# SD_Card_WCN_RF.net
KiCad netlist of a schematic drawn in Altium Designer
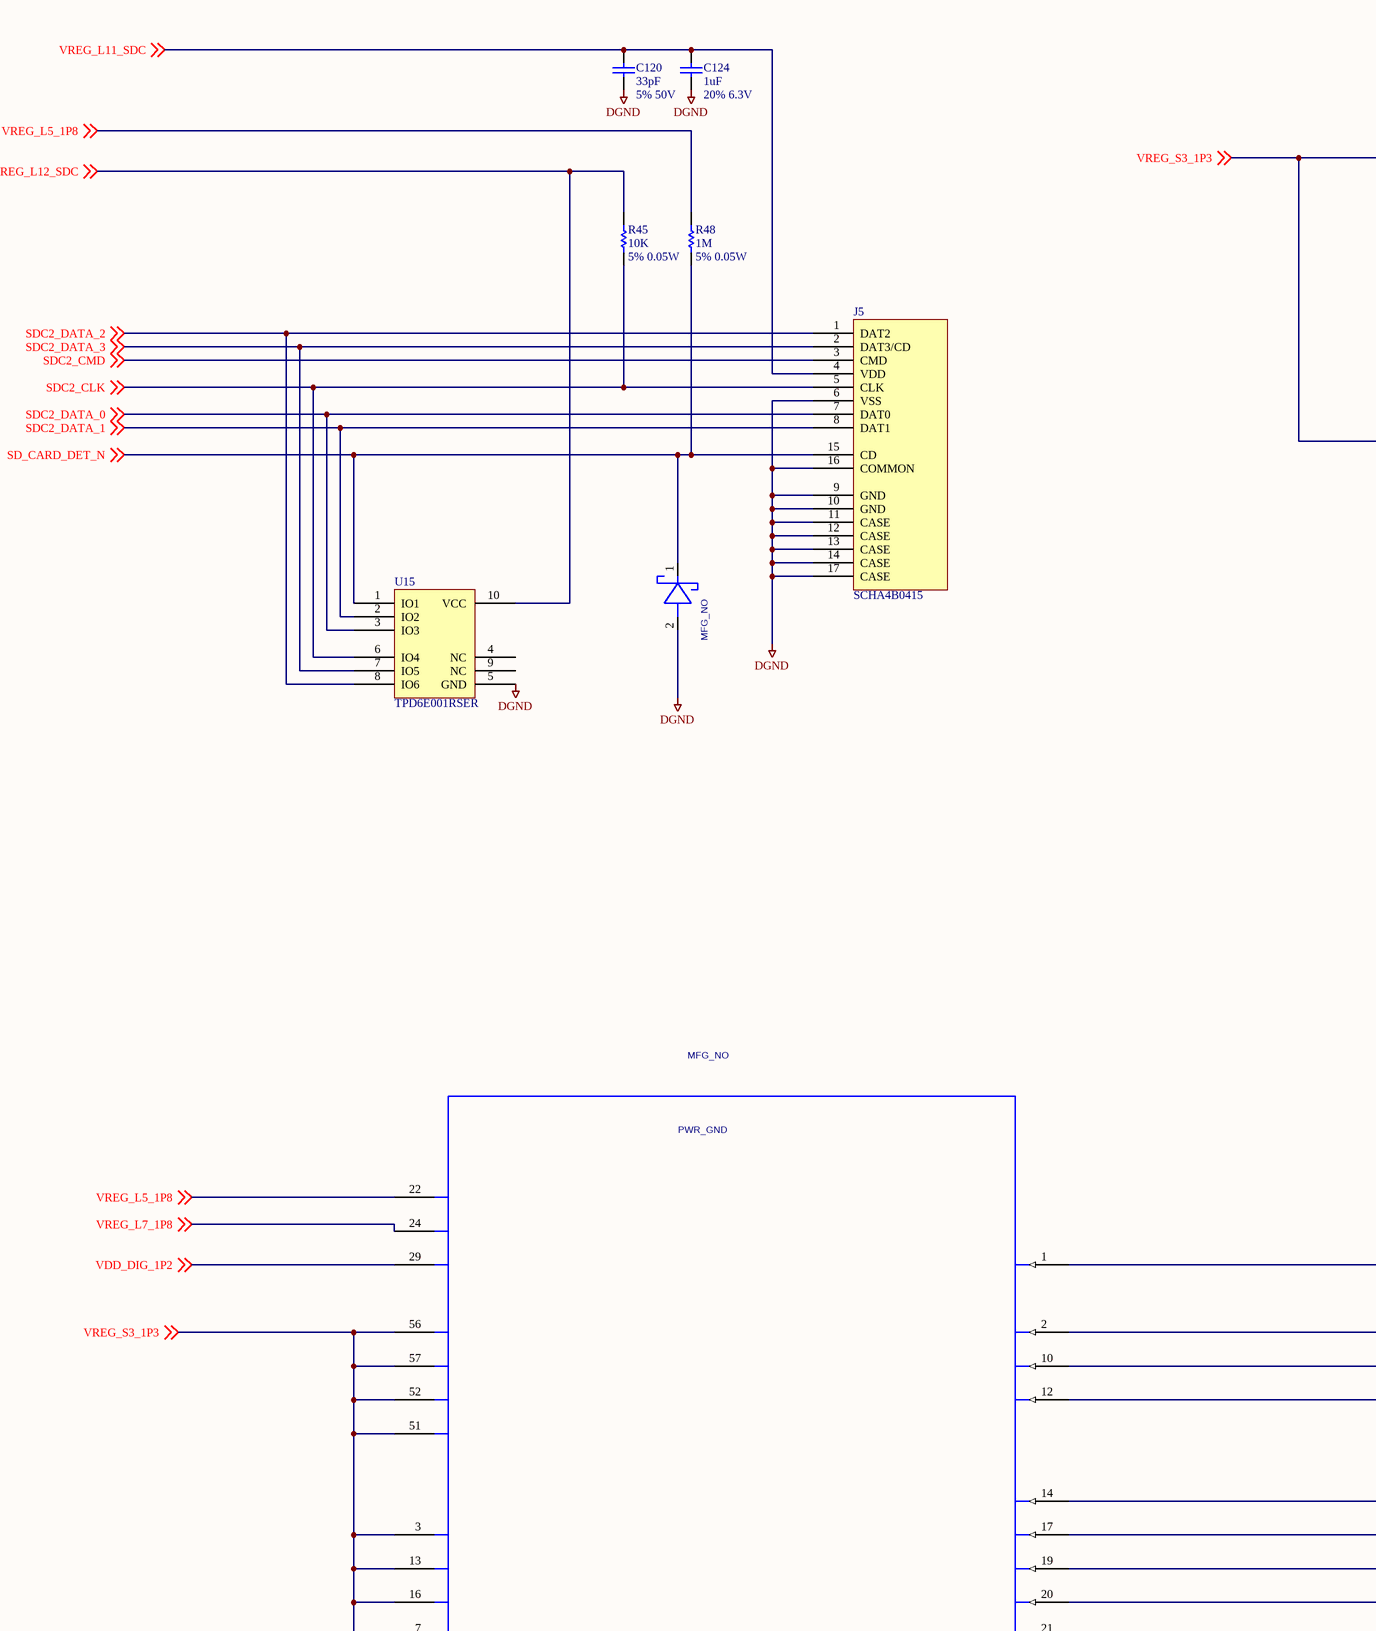
[diagram p0: SD Card_WCN_RF.SchDoc, top left]
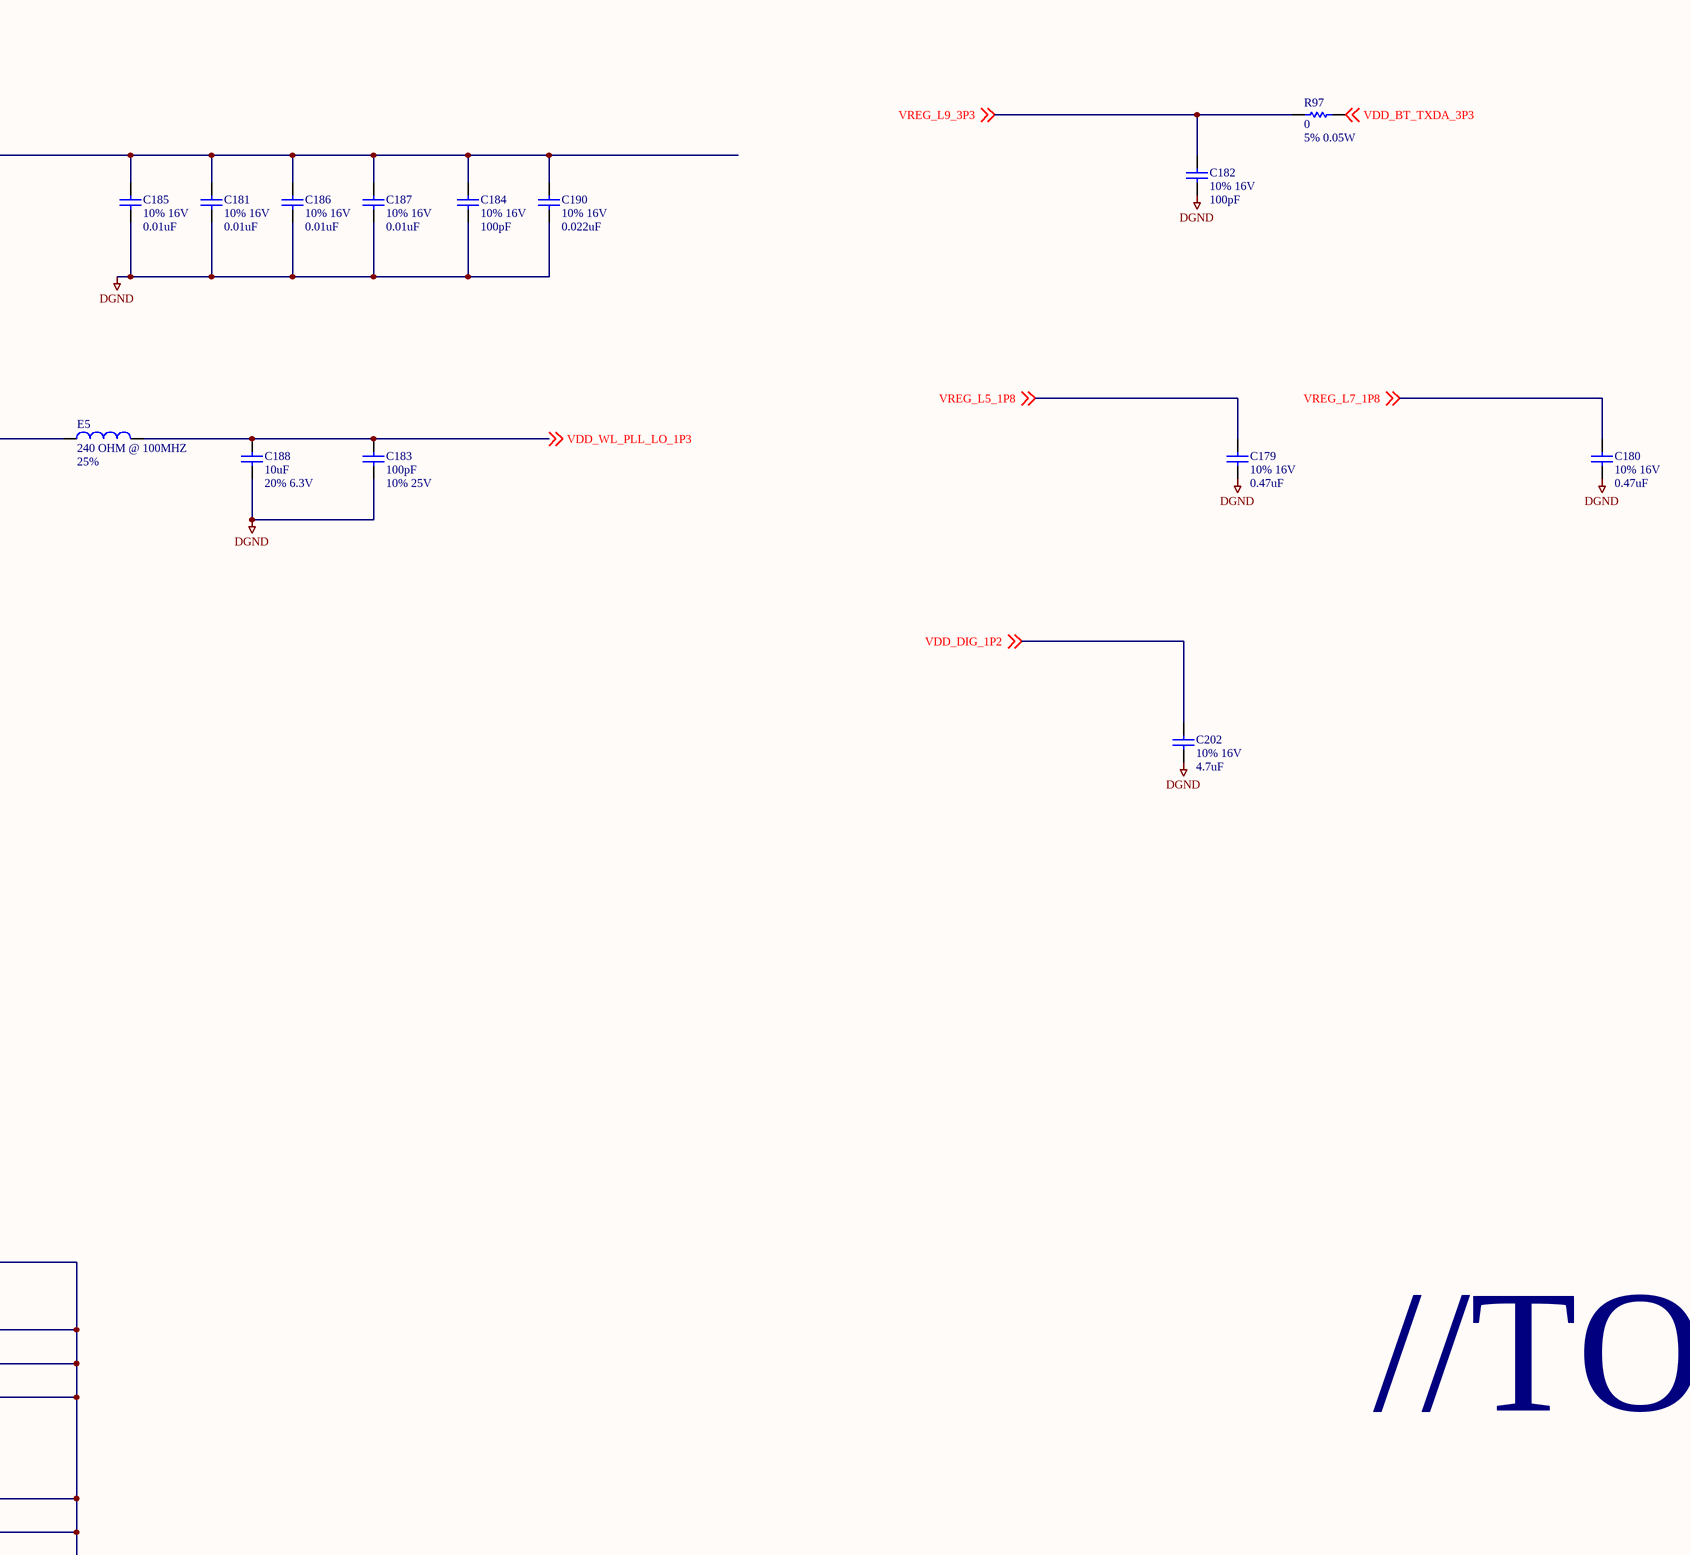
[diagram p1: SD Card_WCN_RF.SchDoc, top middle]
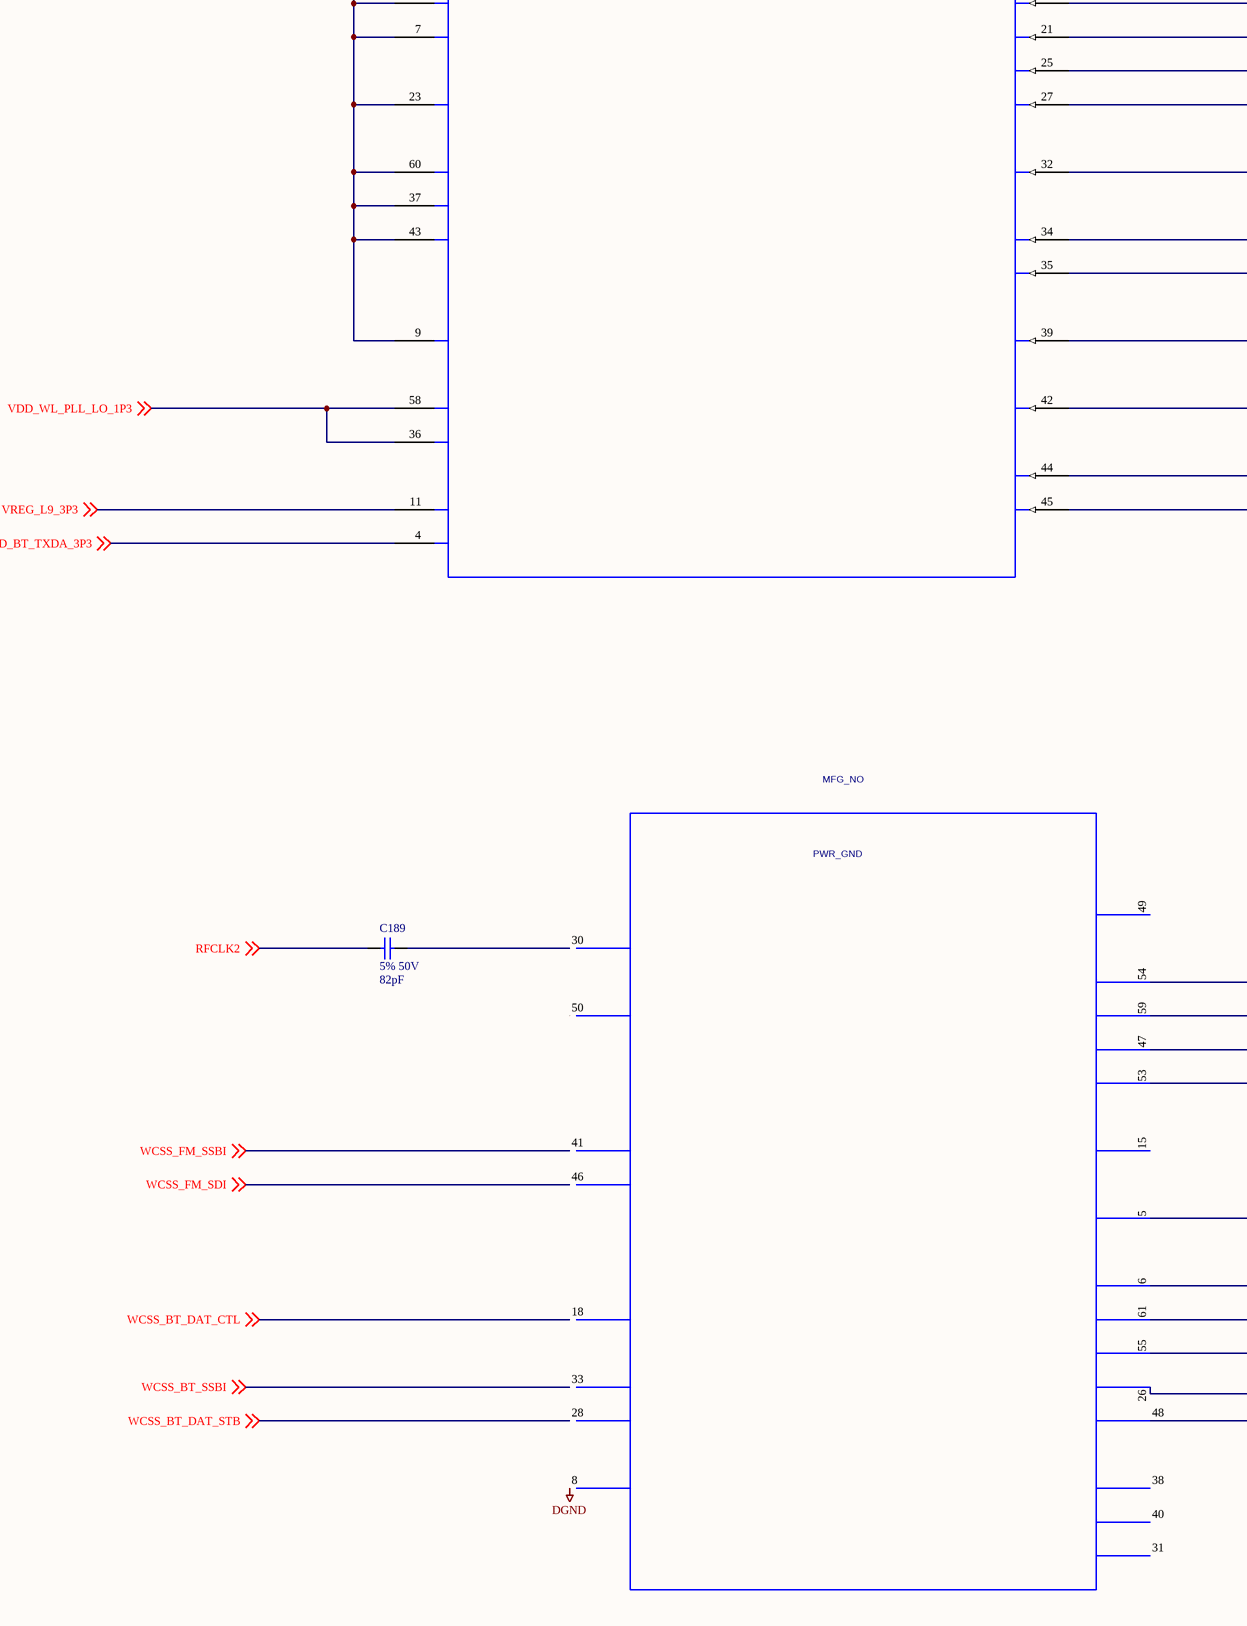
[diagram p2: SD Card_WCN_RF.SchDoc, bottom left]
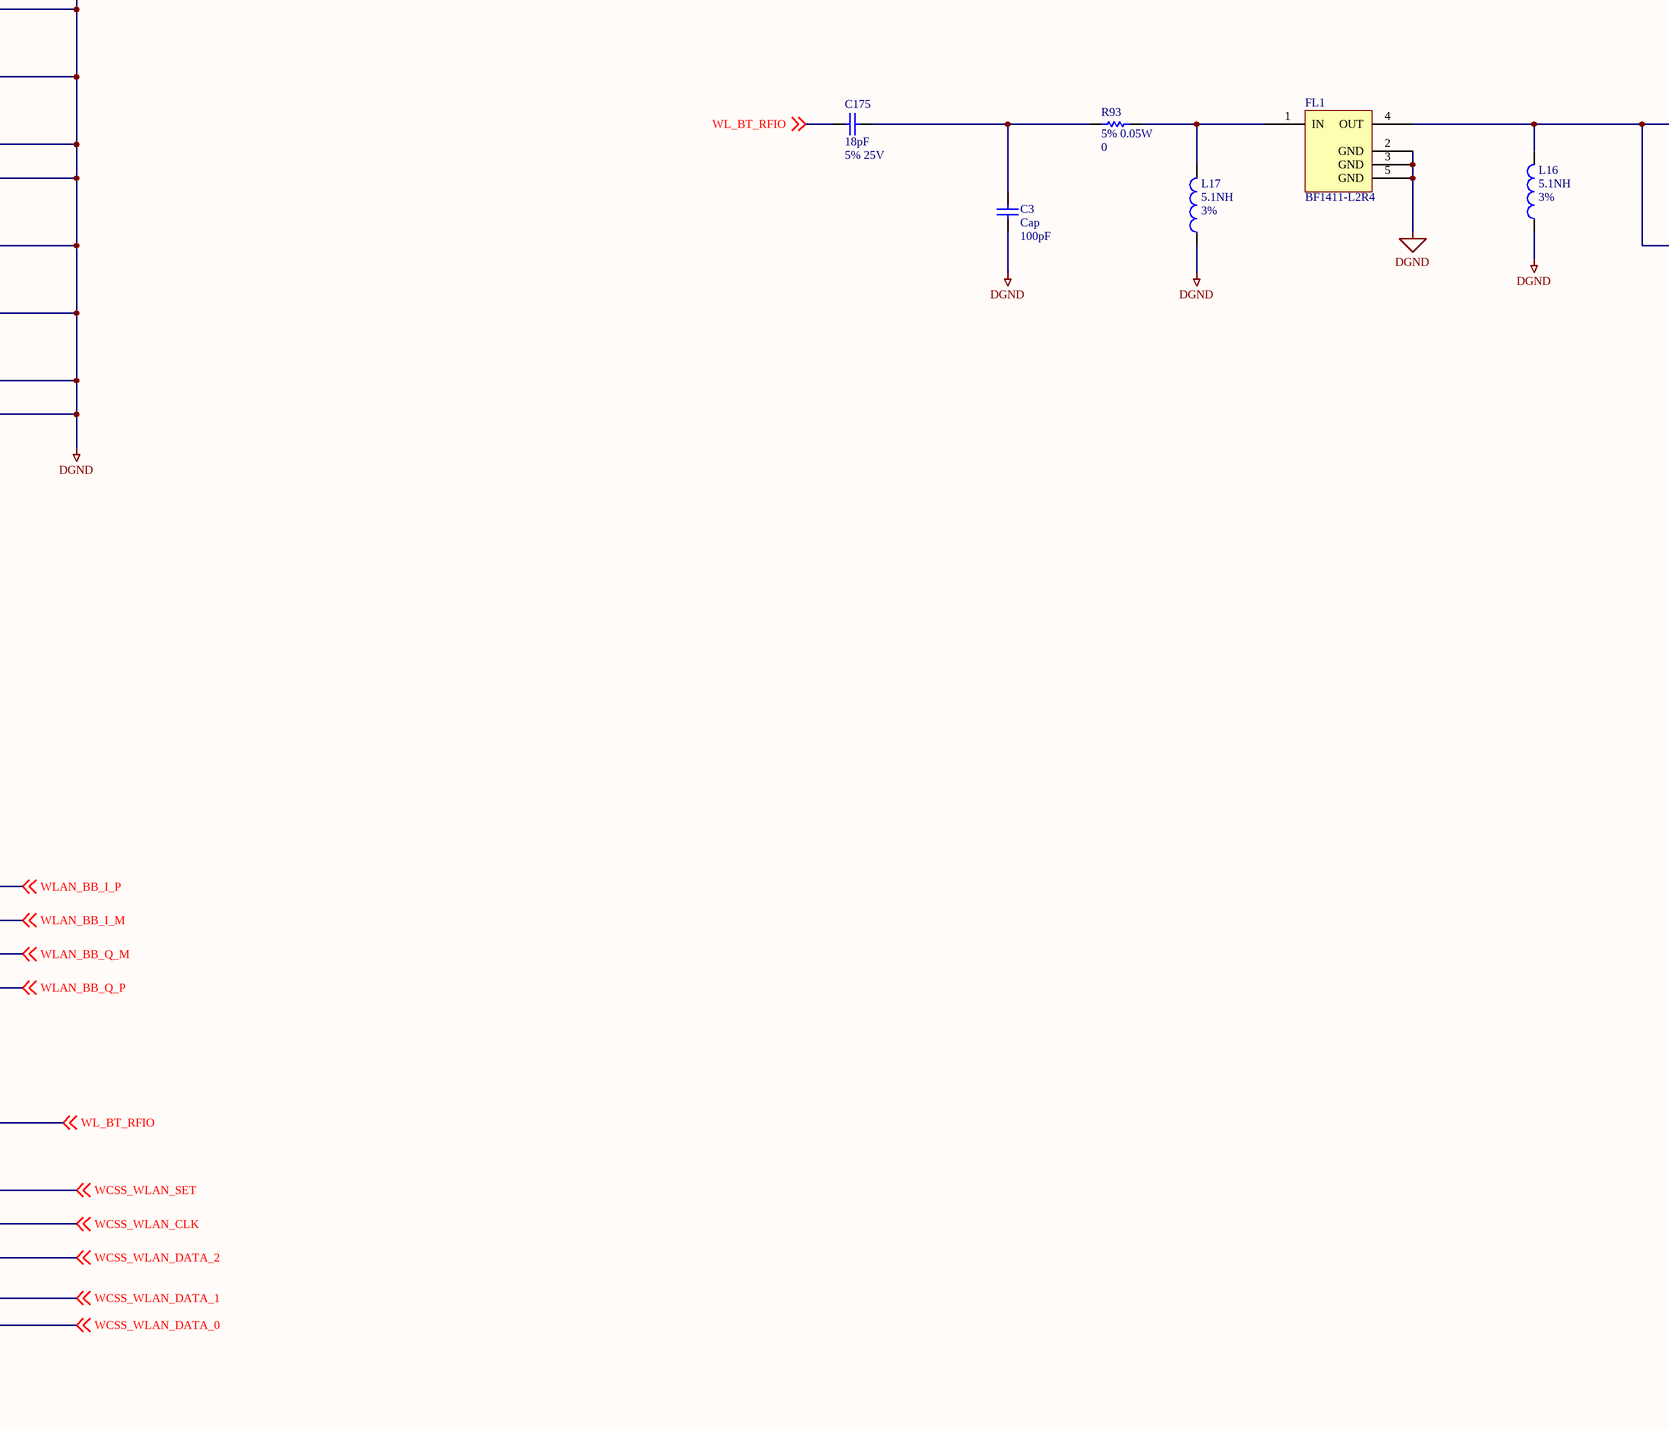
[diagram p3: SD Card_WCN_RF.SchDoc, bottom middle]
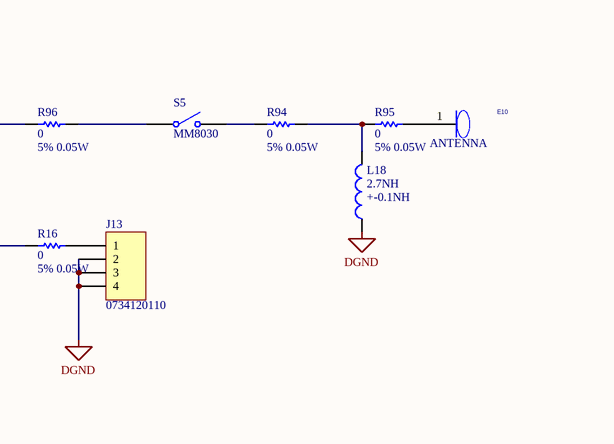
[diagram p4: SD Card_WCN_RF.SchDoc, bottom right]

(export (version "E")
  (design (tool "Eeschema 10.0.6"))
  (components
    (comp (ref "C3")
      (value "Cap")
      (footprint "RAD-0.3")
      (description "Capacitor")
      (fields (field (name "ALTIUM_VALUE") "100pF") (field (name "PUBLISHER") "Altium Limited"))
      (libsource (lib "Miscellaneous Devices") (part "Cap"))
    )
    (comp (ref "C120")
      (value "33pF")
      (footprint "C0402")
      (description "Capacitor")
      (fields (field (name "ALTIUM_VALUE") "5% 50V") (field (name "PUBLISHER") "Altium Limited"))
      (libsource (lib "Miscellaneous Devices") (part "Cap"))
    )
    (comp (ref "C124")
      (value "1uF")
      (footprint "C0402")
      (description "Capacitor")
      (fields (field (name "ALTIUM_VALUE") "20% 6.3V") (field (name "PUBLISHER") "Altium Limited"))
      (libsource (lib "Miscellaneous Devices") (part "Cap"))
    )
    (comp (ref "C175")
      (value "18pF")
      (footprint "RAD-0.3")
      (description "Capacitor")
      (fields (field (name "ALTIUM_VALUE") "5% 25V") (field (name "PUBLISHER") "Altium Limited"))
      (libsource (lib "Miscellaneous Devices") (part "Cap"))
    )
    (comp (ref "C179")
      (value "10% 16V")
      (footprint "C0402")
      (description "Capacitor")
      (fields (field (name "ALTIUM_VALUE") "0.47uF") (field (name "PUBLISHER") "Altium Limited"))
      (libsource (lib "Miscellaneous Devices") (part "Cap"))
    )
    (comp (ref "C180")
      (value "10% 16V")
      (footprint "C0402")
      (description "Capacitor")
      (fields (field (name "ALTIUM_VALUE") "0.47uF") (field (name "PUBLISHER") "Altium Limited"))
      (libsource (lib "Miscellaneous Devices") (part "Cap"))
    )
    (comp (ref "C181")
      (value "10% 16V")
      (footprint "C0402")
      (description "Capacitor")
      (fields (field (name "ALTIUM_VALUE") "0.01uF") (field (name "PUBLISHER") "Altium Limited"))
      (libsource (lib "Miscellaneous Devices") (part "Cap"))
    )
    (comp (ref "C182")
      (value "10% 16V")
      (footprint "C0402")
      (description "Capacitor")
      (fields (field (name "ALTIUM_VALUE") "100pF") (field (name "PUBLISHER") "Altium Limited"))
      (libsource (lib "Miscellaneous Devices") (part "Cap"))
    )
    (comp (ref "C183")
      (value "100pF")
      (footprint "C0402")
      (description "Capacitor")
      (fields (field (name "ALTIUM_VALUE") "10% 25V") (field (name "PUBLISHER") "Altium Limited"))
      (libsource (lib "Miscellaneous Devices") (part "Cap"))
    )
    (comp (ref "C184")
      (value "10% 16V")
      (footprint "C0402")
      (description "Capacitor")
      (fields (field (name "ALTIUM_VALUE") "100pF") (field (name "PUBLISHER") "Altium Limited"))
      (libsource (lib "Miscellaneous Devices") (part "Cap"))
    )
    (comp (ref "C185")
      (value "10% 16V")
      (footprint "C0402")
      (description "Capacitor")
      (fields (field (name "ALTIUM_VALUE") "0.01uF") (field (name "PUBLISHER") "Altium Limited"))
      (libsource (lib "Miscellaneous Devices") (part "Cap"))
    )
    (comp (ref "C186")
      (value "10% 16V")
      (footprint "C0402")
      (description "Capacitor")
      (fields (field (name "ALTIUM_VALUE") "0.01uF") (field (name "PUBLISHER") "Altium Limited"))
      (libsource (lib "Miscellaneous Devices") (part "Cap"))
    )
    (comp (ref "C187")
      (value "10% 16V")
      (footprint "C0402")
      (description "Capacitor")
      (fields (field (name "ALTIUM_VALUE") "0.01uF") (field (name "PUBLISHER") "Altium Limited"))
      (libsource (lib "Miscellaneous Devices") (part "Cap"))
    )
    (comp (ref "C188")
      (value "10uF")
      (footprint "C0402")
      (description "Capacitor")
      (fields (field (name "ALTIUM_VALUE") "20% 6.3V") (field (name "PUBLISHER") "Altium Limited"))
      (libsource (lib "Miscellaneous Devices") (part "Cap"))
    )
    (comp (ref "C189")
      (value "5% 50V")
      (footprint "C0402")
      (description "Capacitor")
      (fields (field (name "ALTIUM_VALUE") "82pF") (field (name "PUBLISHER") "Altium Limited"))
      (libsource (lib "Miscellaneous Devices") (part "Cap"))
    )
    (comp (ref "C190")
      (value "10% 16V")
      (footprint "C0402")
      (description "Capacitor")
      (fields (field (name "ALTIUM_VALUE") "0.022uF") (field (name "PUBLISHER") "Altium Limited"))
      (libsource (lib "Miscellaneous Devices") (part "Cap"))
    )
    (comp (ref "C202")
      (value "10% 16V")
      (footprint "C0402")
      (description "Capacitor")
      (fields (field (name "ALTIUM_VALUE") "4.7uF") (field (name "PUBLISHER") "Altium Limited"))
      (libsource (lib "Miscellaneous Devices") (part "Cap"))
    )
    (comp (ref "CR24")
      (value "ESD7C5")
      (footprint "c0402")
      (fields (field (name "PART_NUMBER") "MCN_NO") (field (name "PART_ID") "MFG_NO"))
      (libsource (lib "MSM8916_DRAM_PMIC_REF_Library") (part "SCHOTTKY"))
    )
    (comp (ref "E5")
      (value "240 OHM @ 100MHZ")
      (footprint "0402-A")
      (description "Inductor")
      (fields (field (name "ALTIUM_VALUE") "25%") (field (name "PUBLISHER") "Altium Limited"))
      (libsource (lib "Miscellaneous Devices") (part "Inductor"))
    )
    (comp (ref "E10")
      (value "ANTENNA")
      (footprint "TP")
      (libsource (lib "MSM8916_DRAM_PMIC_REF_Library") (part "TP"))
    )
    (comp (ref "FL1")
      (value "BF1411-L2R4")
      (libsource (lib "MSM8916_DRAM_PMIC_REF_Library") (part "BF1411-L2R4"))
    )
    (comp (ref "J5")
      (value "SCHA4B0415")
      (footprint "c0402")
      (libsource (lib "MSM8916_DRAM_PMIC_REF_Library") (part "SCHA4B0415"))
    )
    (comp (ref "J13")
      (value "0734120110")
      (footprint "HDR1X4")
      (description "Header, 4-Pin")
      (fields (field (name "PUBLISHER") "Altium Limited"))
      (libsource (lib "Miscellaneous Connectors") (part "Header 4"))
    )
    (comp (ref "L16")
      (value "5.1NH")
      (footprint "0402-A")
      (description "Inductor")
      (fields (field (name "ALTIUM_VALUE") "3%") (field (name "PUBLISHER") "Altium Limited"))
      (libsource (lib "Miscellaneous Devices") (part "Inductor"))
    )
    (comp (ref "L17")
      (value "5.1NH")
      (footprint "0402-A")
      (description "Inductor")
      (fields (field (name "ALTIUM_VALUE") "3%") (field (name "PUBLISHER") "Altium Limited"))
      (libsource (lib "Miscellaneous Devices") (part "Inductor"))
    )
    (comp (ref "L18")
      (value "2.7NH")
      (footprint "0402-A")
      (description "Inductor")
      (fields (field (name "ALTIUM_VALUE") "+-0.1NH") (field (name "PUBLISHER") "Altium Limited"))
      (libsource (lib "Miscellaneous Devices") (part "Inductor"))
    )
    (comp (ref "R16")
      (value "0")
      (footprint "AXIAL-0.3")
      (description "Resistor")
      (fields (field (name "ALTIUM_VALUE") "5% 0.05W") (field (name "PUBLISHER") "Altium Limited"))
      (libsource (lib "Miscellaneous Devices") (part "Res1"))
    )
    (comp (ref "R45")
      (value "10K")
      (footprint "r0402")
      (description "Resistor")
      (fields (field (name "ALTIUM_VALUE") "5% 0.05W") (field (name "PUBLISHER") "Altium Limited"))
      (libsource (lib "Miscellaneous Devices") (part "Res1"))
    )
    (comp (ref "R48")
      (value "1M")
      (footprint "r0402")
      (description "Resistor")
      (fields (field (name "ALTIUM_VALUE") "5% 0.05W") (field (name "PUBLISHER") "Altium Limited"))
      (libsource (lib "Miscellaneous Devices") (part "Res1"))
    )
    (comp (ref "R93")
      (value "5% 0.05W")
      (footprint "AXIAL-0.3")
      (description "Resistor")
      (fields (field (name "ALTIUM_VALUE") "0") (field (name "PUBLISHER") "Altium Limited"))
      (libsource (lib "Miscellaneous Devices") (part "Res1"))
    )
    (comp (ref "R94")
      (value "0")
      (footprint "AXIAL-0.3")
      (description "Resistor")
      (fields (field (name "ALTIUM_VALUE") "5% 0.05W") (field (name "PUBLISHER") "Altium Limited"))
      (libsource (lib "Miscellaneous Devices") (part "Res1"))
    )
    (comp (ref "R95")
      (value "0")
      (footprint "AXIAL-0.3")
      (description "Resistor")
      (fields (field (name "ALTIUM_VALUE") "5% 0.05W") (field (name "PUBLISHER") "Altium Limited"))
      (libsource (lib "Miscellaneous Devices") (part "Res1"))
    )
    (comp (ref "R96")
      (value "0")
      (footprint "AXIAL-0.3")
      (description "Resistor")
      (fields (field (name "ALTIUM_VALUE") "5% 0.05W") (field (name "PUBLISHER") "Altium Limited"))
      (libsource (lib "Miscellaneous Devices") (part "Res1"))
    )
    (comp (ref "R97")
      (value "0")
      (footprint "r0402")
      (description "Resistor")
      (fields (field (name "ALTIUM_VALUE") "5% 0.05W") (field (name "PUBLISHER") "Altium Limited"))
      (libsource (lib "Miscellaneous Devices") (part "Res1"))
    )
    (comp (ref "S5")
      (value "MM8030")
      (footprint "SPST-2")
      (description "Single-Pole, Single-Throw Switch")
      (fields (field (name "PUBLISHER") "Altium Limited"))
      (libsource (lib "Miscellaneous Devices") (part "SW-SPST"))
    )
    (comp (ref "U9")
      (value "ASIC_WCN3620_80_WL006_1")
      (footprint "WCN-3620-0-61WLNSP-TR-05-0")
      (fields
        (field (name "PART_NUMBER") "MCN_NO")
        (field (name "SYMNAME") "PWR_GND")
        (field (name "PART_ID") "MFG_NO")
      )
      (libsource (lib "MSM8916_DRAM_PMIC_REF_Library") (part "ASIC_WCN3620_80_WL006_1"))
    )
    (comp (ref "U15")
      (value "TPD6E001RSER")
      (footprint "c0402")
      (libsource (lib "MSM8916_DRAM_PMIC_REF_Library") (part "TPD6E001RSER"))
    )
  )
  (nets
    (net (code "1") (name "DGND") (class "Default")
      (node (ref "C120") (pin "1") (pinfunction "1_1") (pintype "passive"))
      (node (ref "C124") (pin "1") (pinfunction "1_1") (pintype "passive"))
      (node (ref "C179") (pin "1") (pinfunction "1_1") (pintype "passive"))
      (node (ref "C180") (pin "1") (pinfunction "1_1") (pintype "passive"))
      (node (ref "C181") (pin "1") (pinfunction "1_1") (pintype "passive"))
      (node (ref "C182") (pin "1") (pinfunction "1_1") (pintype "passive"))
      (node (ref "C183") (pin "1") (pinfunction "1_1") (pintype "passive"))
      (node (ref "C184") (pin "1") (pinfunction "1_1") (pintype "passive"))
      (node (ref "C185") (pin "1") (pinfunction "1_1") (pintype "passive"))
      (node (ref "C186") (pin "1") (pinfunction "1_1") (pintype "passive"))
      (node (ref "C187") (pin "1") (pinfunction "1_1") (pintype "passive"))
      (node (ref "C188") (pin "1") (pinfunction "1_1") (pintype "passive"))
      (node (ref "C190") (pin "1") (pinfunction "1_1") (pintype "passive"))
      (node (ref "C202") (pin "1") (pinfunction "1_1") (pintype "passive"))
      (node (ref "C3") (pin "1") (pinfunction "1_1") (pintype "passive"))
      (node (ref "CR24") (pin "2") (pinfunction "POS_2") (pintype "bidirectional"))
      (node (ref "FL1") (pin "2") (pinfunction "GND_2") (pintype "passive"))
      (node (ref "FL1") (pin "3") (pinfunction "GND_3") (pintype "passive"))
      (node (ref "FL1") (pin "5") (pinfunction "GND_5") (pintype "passive"))
      (node (ref "J13") (pin "2") (pinfunction "2_2") (pintype "passive"))
      (node (ref "J13") (pin "3") (pinfunction "3_3") (pintype "passive"))
      (node (ref "J13") (pin "4") (pinfunction "4_4") (pintype "passive"))
      (node (ref "J5") (pin "10") (pinfunction "GND_10") (pintype "passive"))
      (node (ref "J5") (pin "11") (pinfunction "CASE_11") (pintype "passive"))
      (node (ref "J5") (pin "12") (pinfunction "CASE_12") (pintype "passive"))
      (node (ref "J5") (pin "13") (pinfunction "CASE_13") (pintype "passive"))
      (node (ref "J5") (pin "14") (pinfunction "CASE_14") (pintype "passive"))
      (node (ref "J5") (pin "16") (pinfunction "COMMON_16") (pintype "passive"))
      (node (ref "J5") (pin "17") (pinfunction "CASE_17") (pintype "passive"))
      (node (ref "J5") (pin "6") (pinfunction "VSS_6") (pintype "passive"))
      (node (ref "J5") (pin "9") (pinfunction "GND_9") (pintype "passive"))
      (node (ref "L16") (pin "1") (pinfunction "1_1") (pintype "passive"))
      (node (ref "L17") (pin "1") (pinfunction "1_1") (pintype "passive"))
      (node (ref "L18") (pin "1") (pinfunction "1_1") (pintype "passive"))
      (node (ref "U15") (pin "5") (pinfunction "GND_5") (pintype "passive"))
      (node (ref "U9") (pin "1") (pinfunction "GND2_1") (pintype "input"))
      (node (ref "U9") (pin "10") (pinfunction "GND4_10") (pintype "input"))
      (node (ref "U9") (pin "12") (pinfunction "GND5_12") (pintype "input"))
      (node (ref "U9") (pin "14") (pinfunction "GND6_14") (pintype "input"))
      (node (ref "U9") (pin "17") (pinfunction "GND7_17") (pintype "input"))
      (node (ref "U9") (pin "19") (pinfunction "GND8_19") (pintype "input"))
      (node (ref "U9") (pin "2") (pinfunction "GND3_2") (pintype "input"))
      (node (ref "U9") (pin "20") (pinfunction "GND9_20") (pintype "input"))
      (node (ref "U9") (pin "21") (pinfunction "GND10_21") (pintype "input"))
      (node (ref "U9") (pin "25") (pinfunction "GND11_25") (pintype "input"))
      (node (ref "U9") (pin "27") (pinfunction "GND12_27") (pintype "input"))
      (node (ref "U9") (pin "32") (pinfunction "GND13_32") (pintype "input"))
      (node (ref "U9") (pin "34") (pinfunction "GND14_34") (pintype "input"))
      (node (ref "U9") (pin "35") (pinfunction "GND15_35") (pintype "input"))
      (node (ref "U9") (pin "39") (pinfunction "GND16_39") (pintype "input"))
      (node (ref "U9") (pin "42") (pinfunction "GND17_42") (pintype "input"))
      (node (ref "U9") (pin "44") (pinfunction "GND18_44") (pintype "input"))
      (node (ref "U9") (pin "45") (pinfunction "GND19_45") (pintype "input"))
      (node (ref "U9") (pin "8") (pinfunction "GND1_8") (pintype "input"))
    )
    (net (code "2") (name "Net-(C175-Pad2)") (class "Default")
      (node (ref "C175") (pin "2") (pinfunction "2_2") (pintype "passive"))
      (node (ref "C3") (pin "2") (pinfunction "2_2") (pintype "passive"))
      (node (ref "R93") (pin "1") (pinfunction "1_1") (pintype "passive"))
    )
    (net (code "3") (name "Net-(E10-Pad1)") (class "Default")
      (node (ref "E10") (pin "1") (pinfunction "1_1") (pintype "passive"))
      (node (ref "R95") (pin "2") (pinfunction "2_2") (pintype "passive"))
    )
    (net (code "4") (name "Net-(FL1-IN)") (class "Default")
      (node (ref "FL1") (pin "1") (pinfunction "IN_1") (pintype "passive"))
      (node (ref "L17") (pin "2") (pinfunction "2_2") (pintype "passive"))
      (node (ref "R93") (pin "2") (pinfunction "2_2") (pintype "passive"))
    )
    (net (code "5") (name "Net-(FL1-OUT)") (class "Default")
      (node (ref "FL1") (pin "4") (pinfunction "OUT_4") (pintype "passive"))
      (node (ref "L16") (pin "2") (pinfunction "2_2") (pintype "passive"))
      (node (ref "R16") (pin "1") (pinfunction "1_1") (pintype "passive"))
      (node (ref "R96") (pin "1") (pinfunction "1_1") (pintype "passive"))
    )
    (net (code "6") (name "Net-(J13-Pad1)") (class "Default")
      (node (ref "J13") (pin "1") (pinfunction "1_1") (pintype "passive"))
      (node (ref "R16") (pin "2") (pinfunction "2_2") (pintype "passive"))
    )
    (net (code "7") (name "Net-(L18-Pad2)") (class "Default")
      (node (ref "L18") (pin "2") (pinfunction "2_2") (pintype "passive"))
      (node (ref "R94") (pin "2") (pinfunction "2_2") (pintype "passive"))
      (node (ref "R95") (pin "1") (pinfunction "1_1") (pintype "passive"))
    )
    (net (code "8") (name "Net-(S5-COMMON)") (class "Default")
      (node (ref "R96") (pin "2") (pinfunction "2_2") (pintype "passive"))
      (node (ref "S5") (pin "1") (pinfunction "COMMON_1") (pintype "passive"))
    )
    (net (code "9") (name "Net-(S5-NO)") (class "Default")
      (node (ref "R94") (pin "1") (pinfunction "1_1") (pintype "passive"))
      (node (ref "S5") (pin "2") (pinfunction "NO_2") (pintype "passive"))
    )
    (net (code "10") (name "Net-(U9A-TCXO_IN)") (class "Default")
      (node (ref "C189") (pin "1") (pinfunction "1_1") (pintype "passive"))
      (node (ref "U9") (pin "30") (pinfunction "TCXO_IN_30") (pintype "bidirectional"))
    )
    (net (code "11") (name "RFCLK2") (class "Default")
      (node (ref "C189") (pin "2") (pinfunction "2_2") (pintype "passive"))
    )
    (net (code "12") (name "SDC2_CLK") (class "Default")
      (node (ref "J5") (pin "5") (pinfunction "CLK_5") (pintype "passive"))
      (node (ref "R45") (pin "1") (pinfunction "1_1") (pintype "passive"))
      (node (ref "U15") (pin "6") (pinfunction "IO4_6") (pintype "passive"))
    )
    (net (code "13") (name "SDC2_CMD") (class "Default")
      (node (ref "J5") (pin "3") (pinfunction "CMD_3") (pintype "passive"))
    )
    (net (code "14") (name "SDC2_DATA_0") (class "Default")
      (node (ref "J5") (pin "7") (pinfunction "DAT0_7") (pintype "passive"))
      (node (ref "U15") (pin "3") (pinfunction "IO3_3") (pintype "passive"))
    )
    (net (code "15") (name "SDC2_DATA_1") (class "Default")
      (node (ref "J5") (pin "8") (pinfunction "DAT1_8") (pintype "passive"))
      (node (ref "U15") (pin "2") (pinfunction "IO2_2") (pintype "passive"))
    )
    (net (code "16") (name "SDC2_DATA_2") (class "Default")
      (node (ref "J5") (pin "1") (pinfunction "DAT2_1") (pintype "passive"))
      (node (ref "U15") (pin "8") (pinfunction "IO6_8") (pintype "passive"))
    )
    (net (code "17") (name "SDC2_DATA_3") (class "Default")
      (node (ref "J5") (pin "2") (pinfunction "DAT3/CD_2") (pintype "passive"))
      (node (ref "U15") (pin "7") (pinfunction "IO5_7") (pintype "passive"))
    )
    (net (code "18") (name "SD_CARD_DET_N") (class "Default")
      (node (ref "CR24") (pin "1") (pinfunction "NEG_1") (pintype "bidirectional"))
      (node (ref "J5") (pin "15") (pinfunction "CD_15") (pintype "passive"))
      (node (ref "R48") (pin "1") (pinfunction "1_1") (pintype "passive"))
      (node (ref "U15") (pin "1") (pinfunction "IO1_1") (pintype "passive"))
    )
    (net (code "19") (name "VDD_BT_TXDA_3P3") (class "Default")
      (node (ref "R97") (pin "2") (pinfunction "2_2") (pintype "passive"))
      (node (ref "U9") (pin "4") (pinfunction "VDD_BT_DA_3P0_4") (pintype "power_in"))
    )
    (net (code "20") (name "VDD_DIG_1P2") (class "Default")
      (node (ref "C202") (pin "2") (pinfunction "2_2") (pintype "passive"))
      (node (ref "U9") (pin "29") (pinfunction "VDD_DIG_1P2_29") (pintype "power_in"))
    )
    (net (code "21") (name "VDD_WL_PLL_LO_1P3") (class "Default")
      (node (ref "C183") (pin "2") (pinfunction "2_2") (pintype "passive"))
      (node (ref "C188") (pin "2") (pinfunction "2_2") (pintype "passive"))
      (node (ref "E5") (pin "2") (pinfunction "2_2") (pintype "passive"))
      (node (ref "U9") (pin "36") (pinfunction "VDD_WL_LO_1P3_36") (pintype "power_in"))
      (node (ref "U9") (pin "58") (pinfunction "VDD_WL_PLL_1P3_58") (pintype "power_in"))
    )
    (net (code "22") (name "VREG_L5_1P8") (class "Default")
      (node (ref "C179") (pin "2") (pinfunction "2_2") (pintype "passive"))
      (node (ref "R48") (pin "2") (pinfunction "2_2") (pintype "passive"))
      (node (ref "U9") (pin "22") (pinfunction "VDD_IO_1P8_22") (pintype "power_in"))
    )
    (net (code "23") (name "VREG_L7_1P8") (class "Default")
      (node (ref "C180") (pin "2") (pinfunction "2_2") (pintype "passive"))
      (node (ref "U9") (pin "24") (pinfunction "VDD_XO_1P8_24") (pintype "power_in"))
    )
    (net (code "24") (name "VREG_L9_3P3") (class "Default")
      (node (ref "C182") (pin "2") (pinfunction "2_2") (pintype "passive"))
      (node (ref "R97") (pin "1") (pinfunction "1_1") (pintype "passive"))
      (node (ref "U9") (pin "11") (pinfunction "VDD_WL_2GPA_3P0_11") (pintype "power_in"))
    )
    (net (code "25") (name "VREG_L11_SDC") (class "Default")
      (node (ref "C120") (pin "2") (pinfunction "2_2") (pintype "passive"))
      (node (ref "C124") (pin "2") (pinfunction "2_2") (pintype "passive"))
      (node (ref "J5") (pin "4") (pinfunction "VDD_4") (pintype "passive"))
    )
    (net (code "26") (name "VREG_L12_SDC") (class "Default")
      (node (ref "R45") (pin "2") (pinfunction "2_2") (pintype "passive"))
      (node (ref "U15") (pin "10") (pinfunction "VCC_10") (pintype "passive"))
    )
    (net (code "27") (name "VREG_S3_1P3") (class "Default")
      (node (ref "C181") (pin "2") (pinfunction "2_2") (pintype "passive"))
      (node (ref "C184") (pin "2") (pinfunction "2_2") (pintype "passive"))
      (node (ref "C185") (pin "2") (pinfunction "2_2") (pintype "passive"))
      (node (ref "C186") (pin "2") (pinfunction "2_2") (pintype "passive"))
      (node (ref "C187") (pin "2") (pinfunction "2_2") (pintype "passive"))
      (node (ref "C190") (pin "2") (pinfunction "2_2") (pintype "passive"))
      (node (ref "E5") (pin "1") (pinfunction "1_1") (pintype "passive"))
      (node (ref "U9") (pin "13") (pinfunction "VDD_BT_BB_1P3_13") (pintype "power_in"))
      (node (ref "U9") (pin "16") (pinfunction "VDD_BT_PLL_1P3_16") (pintype "power_in"))
      (node (ref "U9") (pin "23") (pinfunction "VDD_BT_FM_DIG_1P3_23") (pintype "power_in"))
      (node (ref "U9") (pin "3") (pinfunction "VDD_BT_RF_1P3_3") (pintype "power_in"))
      (node (ref "U9") (pin "37") (pinfunction "VDD_WL_2GPA_1P3_37") (pintype "power_in"))
      (node (ref "U9") (pin "43") (pinfunction "VDD_WL_UPC_1P3_43") (pintype "power_in"))
      (node (ref "U9") (pin "51") (pinfunction "VDD_FM_VCO_1P3_51") (pintype "power_in"))
      (node (ref "U9") (pin "52") (pinfunction "VDD_FM_PLL_1P3_52") (pintype "power_in"))
      (node (ref "U9") (pin "56") (pinfunction "VDD_FM_RXFE_1P3_56") (pintype "power_in"))
      (node (ref "U9") (pin "57") (pinfunction "VDD_FM_RXBB_1P3_57") (pintype "power_in"))
      (node (ref "U9") (pin "60") (pinfunction "VDD_WL_BB_1P3_60") (pintype "power_in"))
      (node (ref "U9") (pin "7") (pinfunction "VDD_BT_VCO_1P3_7") (pintype "power_in"))
      (node (ref "U9") (pin "9") (pinfunction "VDD_WL_2GLNA_1P3_9") (pintype "power_in"))
    )
    (net (code "28") (name "WCSS_BT_DAT_CTL") (class "Default")
      (node (ref "U9") (pin "18") (pinfunction "BT_CTL_18") (pintype "bidirectional"))
    )
    (net (code "29") (name "WCSS_BT_DAT_STB") (class "Default")
      (node (ref "U9") (pin "28") (pinfunction "BT_DATA_28") (pintype "bidirectional"))
    )
    (net (code "30") (name "WCSS_BT_SSBI") (class "Default")
      (node (ref "U9") (pin "33") (pinfunction "BT_SSBI_33") (pintype "bidirectional"))
    )
    (net (code "31") (name "WCSS_FM_SDI") (class "Default")
      (node (ref "U9") (pin "46") (pinfunction "FM_DATA_46") (pintype "bidirectional"))
    )
    (net (code "32") (name "WCSS_FM_SSBI") (class "Default")
      (node (ref "U9") (pin "41") (pinfunction "FM_SSBI_41") (pintype "bidirectional"))
    )
    (net (code "33") (name "WCSS_WLAN_CLK") (class "Default")
      (node (ref "U9") (pin "61") (pinfunction "WL_CMD_CLK_61") (pintype "bidirectional"))
    )
    (net (code "34") (name "WCSS_WLAN_DATA_0") (class "Default")
      (node (ref "U9") (pin "48") (pinfunction "WL_CMD_DATA0_48") (pintype "bidirectional"))
    )
    (net (code "35") (name "WCSS_WLAN_DATA_1") (class "Default")
      (node (ref "U9") (pin "26") (pinfunction "WL_CMD_DATA1_26") (pintype "bidirectional"))
    )
    (net (code "36") (name "WCSS_WLAN_DATA_2") (class "Default")
      (node (ref "U9") (pin "55") (pinfunction "WL_CMD_DATA2_55") (pintype "bidirectional"))
    )
    (net (code "37") (name "WCSS_WLAN_SET") (class "Default")
      (node (ref "U9") (pin "6") (pinfunction "WL_CMD_SET_6") (pintype "bidirectional"))
    )
    (net (code "38") (name "WLAN_BB_I_M") (class "Default")
      (node (ref "U9") (pin "59") (pinfunction "WL_BB_IN_59") (pintype "bidirectional"))
    )
    (net (code "39") (name "WLAN_BB_I_P") (class "Default")
      (node (ref "U9") (pin "54") (pinfunction "WL_BB_IP_54") (pintype "bidirectional"))
    )
    (net (code "40") (name "WLAN_BB_Q_M") (class "Default")
      (node (ref "U9") (pin "47") (pinfunction "WL_BB_QN_47") (pintype "bidirectional"))
    )
    (net (code "41") (name "WLAN_BB_Q_P") (class "Default")
      (node (ref "U9") (pin "53") (pinfunction "WL_BB_QP_53") (pintype "bidirectional"))
    )
    (net (code "42") (name "WL_BT_RFIO") (class "Default")
      (node (ref "C175") (pin "1") (pinfunction "1_1") (pintype "passive"))
      (node (ref "U9") (pin "5") (pinfunction "WL_BT_RFIO_5") (pintype "bidirectional"))
    )
    (net (code "43") (name "unconnected-(U9A-FM_HS_RX-Pad50)") (class "Default")
      (node (ref "U9") (pin "50") (pinfunction "FM_HS_RX_50") (pintype "bidirectional"))
    )
    (net (code "44") (name "unconnected-(U9A-NC1-Pad15)") (class "Default")
      (node (ref "U9") (pin "15") (pinfunction "NC1_15") (pintype "bidirectional"))
    )
    (net (code "45") (name "unconnected-(U9A-NC2-Pad31)") (class "Default")
      (node (ref "U9") (pin "31") (pinfunction "NC2_31") (pintype "bidirectional"))
    )
    (net (code "46") (name "unconnected-(U9A-NC3-Pad40)") (class "Default")
      (node (ref "U9") (pin "40") (pinfunction "NC3_40") (pintype "bidirectional"))
    )
    (net (code "47") (name "unconnected-(U9A-NC4-Pad38)") (class "Default")
      (node (ref "U9") (pin "38") (pinfunction "NC4_38") (pintype "bidirectional"))
    )
    (net (code "48") (name "unconnected-(U9A-WL_PDET_IN-Pad49)") (class "Default")
      (node (ref "U9") (pin "49") (pinfunction "WL_PDET_IN_49") (pintype "bidirectional"))
    )
    (net (code "49") (name "unconnected-(U15-NC-Pad4)") (class "Default")
      (node (ref "U15") (pin "4") (pinfunction "NC_4") (pintype "passive"))
    )
    (net (code "50") (name "unconnected-(U15-NC-Pad9)") (class "Default")
      (node (ref "U15") (pin "9") (pinfunction "NC_9") (pintype "passive"))
    )
  )
)
